# ORing_block.net
KiCad netlist of a schematic drawn in EAGLE
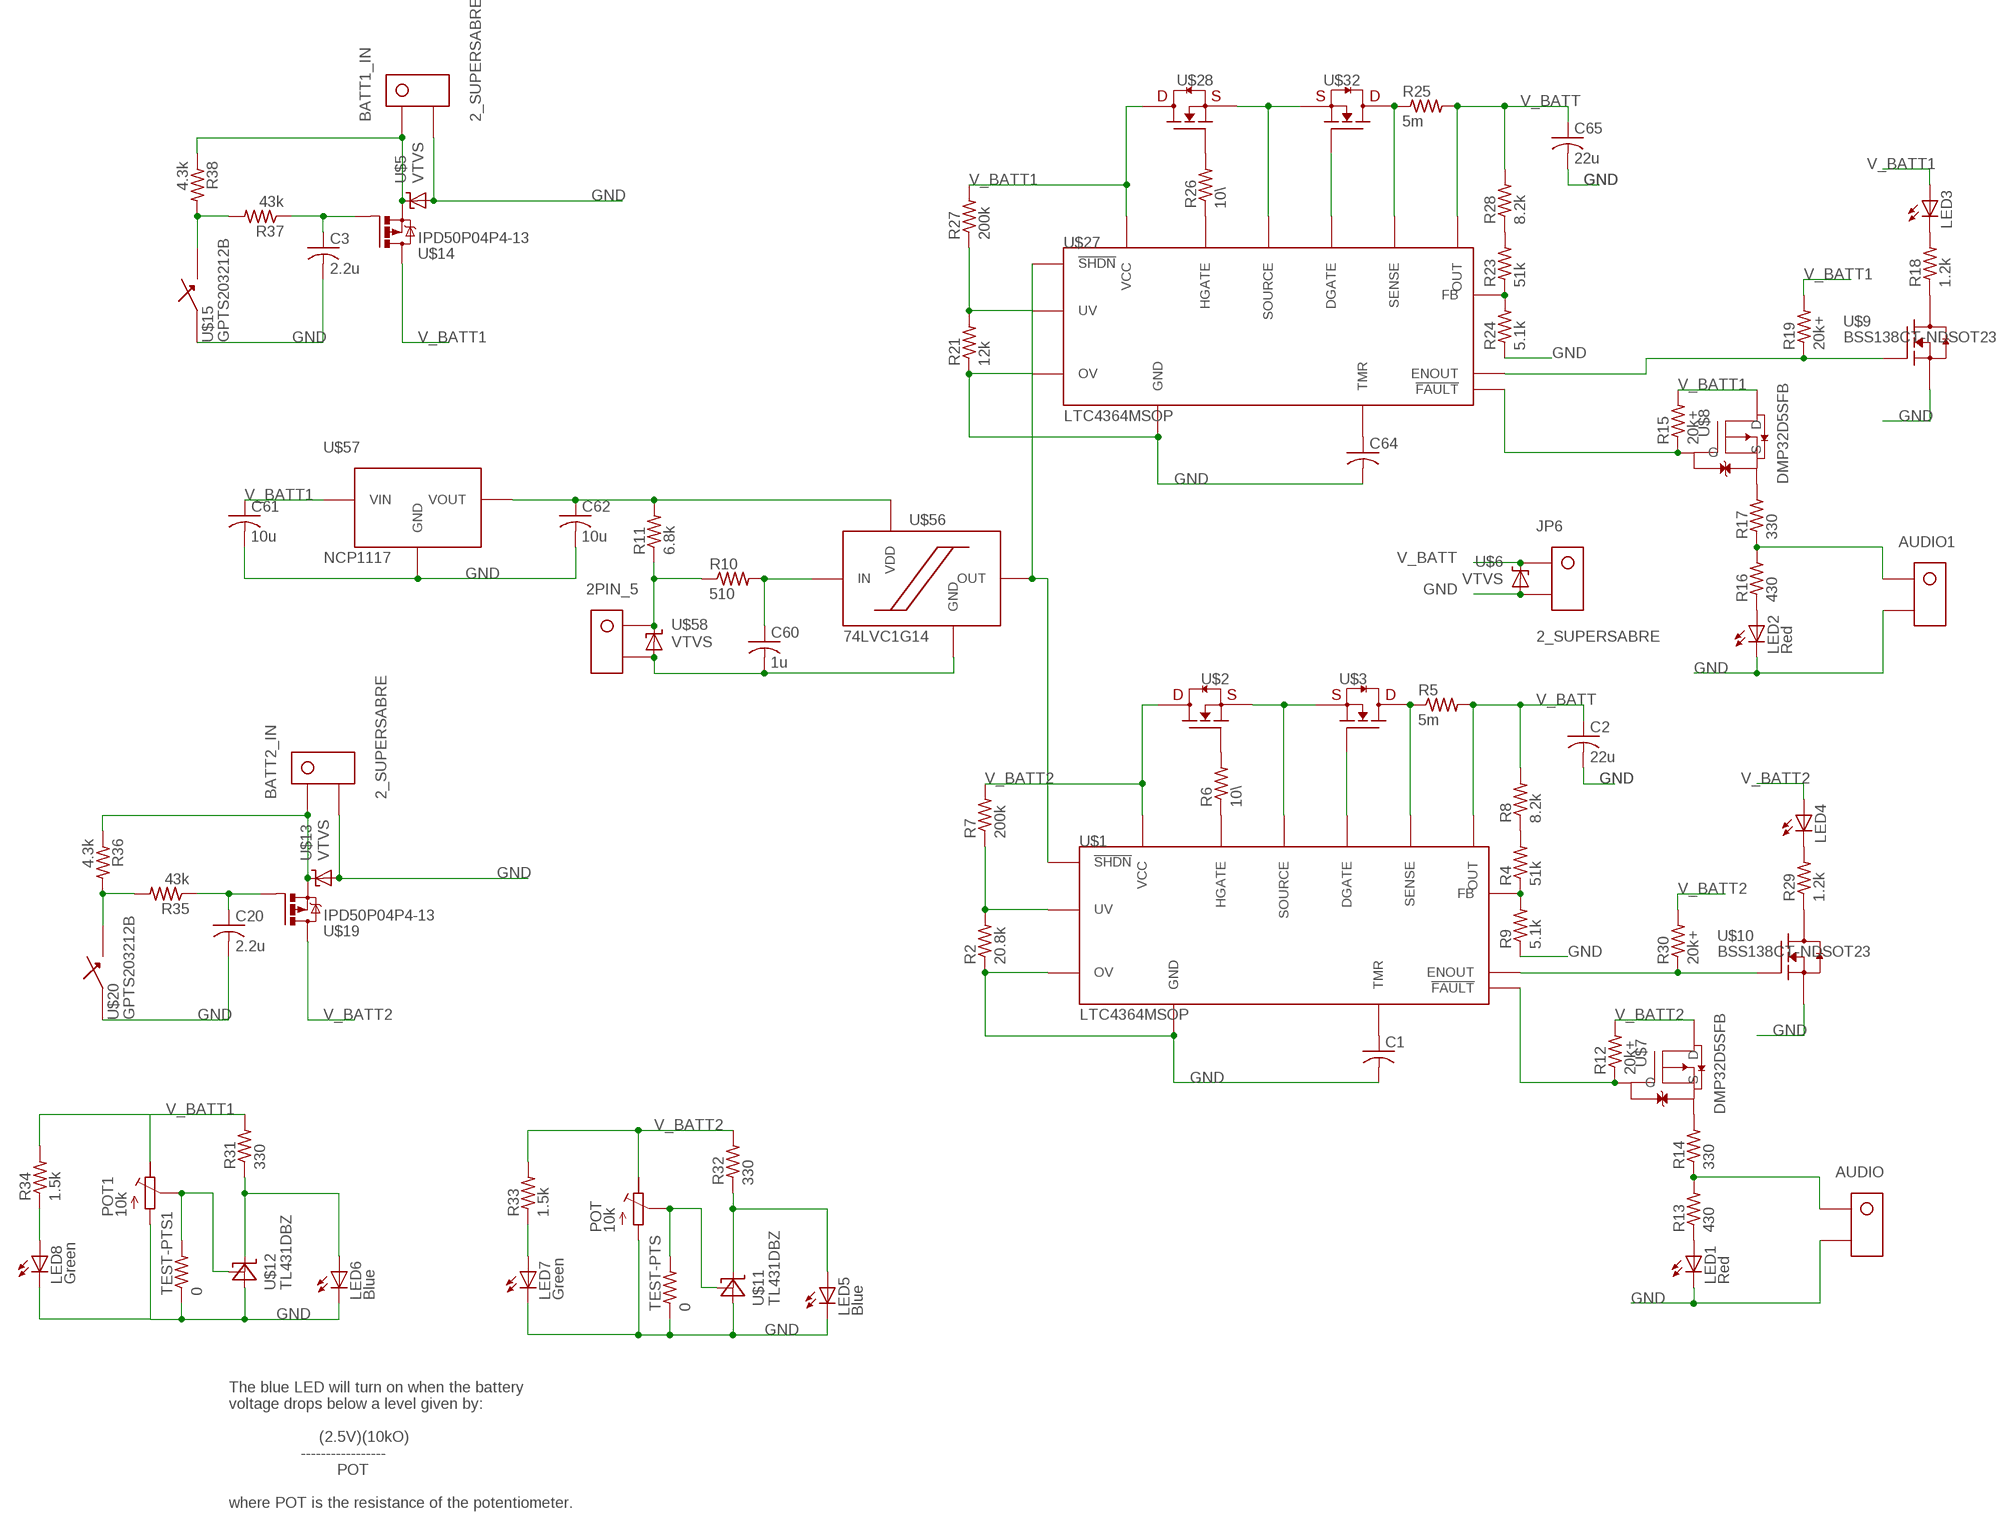
[diagram p0: schematic, sheet 1]

(export (version "E")
  (design (tool "Eeschema 10.0.6"))
  (components
    (comp (ref "2PIN_5")
      (value "KK254_VERT_2PIN22-29-2021")
      (footprint "eagle-import:KK254_VERT_2PIN")
      (libsource (lib "eagle-import") (part "KK254_VERT_2PIN22-29-2021"))
    )
    (comp (ref "AUDIO")
      (value "KK254_VERT_2PIN22-29-2021")
      (footprint "eagle-import:KK254_VERT_2PIN")
      (libsource (lib "eagle-import") (part "KK254_VERT_2PIN22-29-2021"))
    )
    (comp (ref "AUDIO1")
      (value "KK254_VERT_2PIN22-29-2021")
      (footprint "eagle-import:KK254_VERT_2PIN")
      (libsource (lib "eagle-import") (part "KK254_VERT_2PIN22-29-2021"))
    )
    (comp (ref "BATT1_IN")
      (value "2_SUPERSABRE")
      (footprint "eagle-import:SUPERSABRE_2CIRCUIT")
      (libsource (lib "eagle-import") (part "2_SUPERSABRE"))
    )
    (comp (ref "BATT2_IN")
      (value "2_SUPERSABRE")
      (footprint "eagle-import:SUPERSABRE_2CIRCUIT")
      (libsource (lib "eagle-import") (part "2_SUPERSABRE"))
    )
    (comp (ref "C1")
      (value "C-USC0805")
      (footprint "eagle-import:C0805")
      (libsource (lib "eagle-import") (part "C-USC0805"))
    )
    (comp (ref "C2")
      (value "22u")
      (footprint "eagle-import:C0805")
      (libsource (lib "eagle-import") (part "C-USC0805"))
    )
    (comp (ref "C3")
      (value "2.2u")
      (footprint "eagle-import:C0805")
      (libsource (lib "eagle-import") (part "C-USC0805"))
    )
    (comp (ref "C20")
      (value "2.2u")
      (footprint "eagle-import:C0805")
      (libsource (lib "eagle-import") (part "C-USC0805"))
    )
    (comp (ref "C60")
      (value "1u")
      (footprint "eagle-import:C0805")
      (libsource (lib "eagle-import") (part "C-USC0805"))
    )
    (comp (ref "C61")
      (value "10u")
      (footprint "eagle-import:C0805")
      (libsource (lib "eagle-import") (part "C-USC0805"))
    )
    (comp (ref "C62")
      (value "10u")
      (footprint "eagle-import:C0805")
      (libsource (lib "eagle-import") (part "C-USC0805"))
    )
    (comp (ref "C64")
      (value "C-USC0805")
      (footprint "eagle-import:C0805")
      (libsource (lib "eagle-import") (part "C-USC0805"))
    )
    (comp (ref "C65")
      (value "22u")
      (footprint "eagle-import:C0805")
      (libsource (lib "eagle-import") (part "C-USC0805"))
    )
    (comp (ref "JP6")
      (value "2_SUPERSABRE")
      (footprint "eagle-import:SUPERSABRE_2CIRCUIT")
      (libsource (lib "eagle-import") (part "2_SUPERSABRE"))
    )
    (comp (ref "LED1")
      (value "Red")
      (footprint "eagle-import:CHIPLED_0805")
      (libsource (lib "eagle-import") (part "LEDCHIPLED_0805"))
    )
    (comp (ref "LED2")
      (value "Red")
      (footprint "eagle-import:CHIPLED_0805")
      (libsource (lib "eagle-import") (part "LEDCHIPLED_0805"))
    )
    (comp (ref "LED3")
      (value "LEDCHIPLED_0805")
      (footprint "eagle-import:CHIPLED_0805")
      (libsource (lib "eagle-import") (part "LEDCHIPLED_0805"))
    )
    (comp (ref "LED4")
      (value "LEDCHIPLED_0805")
      (footprint "eagle-import:CHIPLED_0805")
      (libsource (lib "eagle-import") (part "LEDCHIPLED_0805"))
    )
    (comp (ref "LED5")
      (value "Blue")
      (footprint "eagle-import:0805")
      (libsource (lib "eagle-import") (part "0805_LED"))
    )
    (comp (ref "LED6")
      (value "Blue")
      (footprint "eagle-import:0805")
      (libsource (lib "eagle-import") (part "0805_LED"))
    )
    (comp (ref "LED7")
      (value "Green")
      (footprint "eagle-import:0805")
      (libsource (lib "eagle-import") (part "0805_LED"))
    )
    (comp (ref "LED8")
      (value "Green")
      (footprint "eagle-import:0805")
      (libsource (lib "eagle-import") (part "0805_LED"))
    )
    (comp (ref "POT")
      (value "10k")
      (footprint "eagle-import:PTV09A-4")
      (libsource (lib "eagle-import") (part "R-TRIMMPTV09A-4"))
    )
    (comp (ref "POT1")
      (value "10k")
      (footprint "eagle-import:PTV09A-4")
      (libsource (lib "eagle-import") (part "R-TRIMMPTV09A-4"))
    )
    (comp (ref "R2")
      (value "20.8k")
      (footprint "eagle-import:R0805")
      (libsource (lib "eagle-import") (part "R-US_R0805"))
    )
    (comp (ref "R4")
      (value "51k")
      (footprint "eagle-import:R0805")
      (libsource (lib "eagle-import") (part "R-US_R0805"))
    )
    (comp (ref "R5")
      (value "5m")
      (footprint "eagle-import:R0805")
      (libsource (lib "eagle-import") (part "R-US_R0805"))
    )
    (comp (ref "R6")
      (value "10\\")
      (footprint "eagle-import:R0805")
      (libsource (lib "eagle-import") (part "R-US_R0805"))
    )
    (comp (ref "R7")
      (value "200k")
      (footprint "eagle-import:R0805")
      (libsource (lib "eagle-import") (part "R-US_R0805"))
    )
    (comp (ref "R8")
      (value "8.2k")
      (footprint "eagle-import:R0805")
      (libsource (lib "eagle-import") (part "R-US_R0805"))
    )
    (comp (ref "R9")
      (value "5.1k")
      (footprint "eagle-import:R0805")
      (libsource (lib "eagle-import") (part "R-US_R0805"))
    )
    (comp (ref "R10")
      (value "510")
      (footprint "eagle-import:R0805")
      (libsource (lib "eagle-import") (part "R-US_R0805"))
    )
    (comp (ref "R11")
      (value "6.8k")
      (footprint "eagle-import:R0805")
      (libsource (lib "eagle-import") (part "R-US_R0805"))
    )
    (comp (ref "R12")
      (value "20k+")
      (footprint "eagle-import:R0805")
      (libsource (lib "eagle-import") (part "R-US_R0805"))
    )
    (comp (ref "R13")
      (value "430")
      (footprint "eagle-import:R0805")
      (libsource (lib "eagle-import") (part "R-US_R0805"))
    )
    (comp (ref "R14")
      (value "330")
      (footprint "eagle-import:R0805")
      (libsource (lib "eagle-import") (part "R-US_R0805"))
    )
    (comp (ref "R15")
      (value "20k+")
      (footprint "eagle-import:R0805")
      (libsource (lib "eagle-import") (part "R-US_R0805"))
    )
    (comp (ref "R16")
      (value "430")
      (footprint "eagle-import:R0805")
      (libsource (lib "eagle-import") (part "R-US_R0805"))
    )
    (comp (ref "R17")
      (value "330")
      (footprint "eagle-import:R0805")
      (libsource (lib "eagle-import") (part "R-US_R0805"))
    )
    (comp (ref "R18")
      (value "1.2k")
      (footprint "eagle-import:R0805")
      (libsource (lib "eagle-import") (part "R-US_R0805"))
    )
    (comp (ref "R19")
      (value "20k+")
      (footprint "eagle-import:R0805")
      (libsource (lib "eagle-import") (part "R-US_R0805"))
    )
    (comp (ref "R21")
      (value "12k")
      (footprint "eagle-import:R0805")
      (libsource (lib "eagle-import") (part "R-US_R0805"))
    )
    (comp (ref "R23")
      (value "51k")
      (footprint "eagle-import:R0805")
      (libsource (lib "eagle-import") (part "R-US_R0805"))
    )
    (comp (ref "R24")
      (value "5.1k")
      (footprint "eagle-import:R0805")
      (libsource (lib "eagle-import") (part "R-US_R0805"))
    )
    (comp (ref "R25")
      (value "5m")
      (footprint "eagle-import:R0805")
      (libsource (lib "eagle-import") (part "R-US_R0805"))
    )
    (comp (ref "R26")
      (value "10\\")
      (footprint "eagle-import:R0805")
      (libsource (lib "eagle-import") (part "R-US_R0805"))
    )
    (comp (ref "R27")
      (value "200k")
      (footprint "eagle-import:R0805")
      (libsource (lib "eagle-import") (part "R-US_R0805"))
    )
    (comp (ref "R28")
      (value "8.2k")
      (footprint "eagle-import:R0805")
      (libsource (lib "eagle-import") (part "R-US_R0805"))
    )
    (comp (ref "R29")
      (value "1.2k")
      (footprint "eagle-import:R0805")
      (libsource (lib "eagle-import") (part "R-US_R0805"))
    )
    (comp (ref "R30")
      (value "20k+")
      (footprint "eagle-import:R0805")
      (libsource (lib "eagle-import") (part "R-US_R0805"))
    )
    (comp (ref "R31")
      (value "330")
      (footprint "eagle-import:R0805")
      (libsource (lib "eagle-import") (part "R-US_R0805"))
    )
    (comp (ref "R32")
      (value "330")
      (footprint "eagle-import:R0805")
      (libsource (lib "eagle-import") (part "R-US_R0805"))
    )
    (comp (ref "R33")
      (value "1.5k")
      (footprint "eagle-import:R0805")
      (libsource (lib "eagle-import") (part "R-US_R0805"))
    )
    (comp (ref "R34")
      (value "1.5k")
      (footprint "eagle-import:R0805")
      (libsource (lib "eagle-import") (part "R-US_R0805"))
    )
    (comp (ref "R35")
      (value "43k")
      (footprint "eagle-import:R0805")
      (libsource (lib "eagle-import") (part "R-US_R0805"))
    )
    (comp (ref "R36")
      (value "4.3k")
      (footprint "eagle-import:R0805")
      (libsource (lib "eagle-import") (part "R-US_R0805"))
    )
    (comp (ref "R37")
      (value "43k")
      (footprint "eagle-import:R0805")
      (libsource (lib "eagle-import") (part "R-US_R0805"))
    )
    (comp (ref "R38")
      (value "4.3k")
      (footprint "eagle-import:R0805")
      (libsource (lib "eagle-import") (part "R-US_R0805"))
    )
    (comp (ref "TEST-PTS")
      (value "0")
      (footprint "eagle-import:V526-0")
      (libsource (lib "eagle-import") (part "R-US_V526-0"))
    )
    (comp (ref "TEST-PTS1")
      (value "0")
      (footprint "eagle-import:V526-0")
      (libsource (lib "eagle-import") (part "R-US_V526-0"))
    )
    (comp (ref "U$1")
      (value "LTC4364MSOP")
      (footprint "eagle-import:MSOP16")
      (libsource (lib "eagle-import") (part "LTC4364MSOP"))
    )
    (comp (ref "U$2")
      (value "FDMC8360LET40PWR33")
      (footprint "eagle-import:POWER33")
      (libsource (lib "eagle-import") (part "FDMC8360LET40PWR33"))
    )
    (comp (ref "U$3")
      (value "FDMC8360LET40PWR33")
      (footprint "eagle-import:POWER33")
      (libsource (lib "eagle-import") (part "FDMC8360LET40PWR33"))
    )
    (comp (ref "U$5")
      (value "VTVS")
      (footprint "eagle-import:DO-219AB")
      (libsource (lib "eagle-import") (part "VTVS"))
    )
    (comp (ref "U$6")
      (value "VTVS")
      (footprint "eagle-import:DO-219AB")
      (libsource (lib "eagle-import") (part "VTVS"))
    )
    (comp (ref "U$7")
      (value "DMP32D5SFB")
      (footprint "eagle-import:AP02002")
      (libsource (lib "eagle-import") (part "DMP32D5SFB"))
    )
    (comp (ref "U$8")
      (value "DMP32D5SFB")
      (footprint "eagle-import:AP02002")
      (libsource (lib "eagle-import") (part "DMP32D5SFB"))
    )
    (comp (ref "U$9")
      (value "BSS138CT-NDSOT23")
      (footprint "eagle-import:SOT23")
      (libsource (lib "eagle-import") (part "BSS138CT-NDSOT23"))
    )
    (comp (ref "U$10")
      (value "BSS138CT-NDSOT23")
      (footprint "eagle-import:SOT23")
      (libsource (lib "eagle-import") (part "BSS138CT-NDSOT23"))
    )
    (comp (ref "U$11")
      (value "TL431DBZ")
      (footprint "eagle-import:SOT-23-3")
      (libsource (lib "eagle-import") (part "TL431DBZ"))
    )
    (comp (ref "U$12")
      (value "TL431DBZ")
      (footprint "eagle-import:SOT-23-3")
      (libsource (lib "eagle-import") (part "TL431DBZ"))
    )
    (comp (ref "U$13")
      (value "VTVS")
      (footprint "eagle-import:DO-219AB")
      (libsource (lib "eagle-import") (part "VTVS"))
    )
    (comp (ref "U$14")
      (value "IPD50P04P4-13")
      (footprint "eagle-import:TO252-3")
      (libsource (lib "eagle-import") (part "IPD50P04P4-13"))
    )
    (comp (ref "U$15")
      (value "GPTS203212B")
      (footprint "eagle-import:GPTS203211B")
      (libsource (lib "eagle-import") (part "GPTS203212B"))
    )
    (comp (ref "U$19")
      (value "IPD50P04P4-13")
      (footprint "eagle-import:TO252-3")
      (libsource (lib "eagle-import") (part "IPD50P04P4-13"))
    )
    (comp (ref "U$20")
      (value "GPTS203212B")
      (footprint "eagle-import:GPTS203211B")
      (libsource (lib "eagle-import") (part "GPTS203212B"))
    )
    (comp (ref "U$27")
      (value "LTC4364MSOP")
      (footprint "eagle-import:MSOP16")
      (libsource (lib "eagle-import") (part "LTC4364MSOP"))
    )
    (comp (ref "U$28")
      (value "FDMC8360LET40PWR33")
      (footprint "eagle-import:POWER33")
      (libsource (lib "eagle-import") (part "FDMC8360LET40PWR33"))
    )
    (comp (ref "U$32")
      (value "FDMC8360LET40PWR33")
      (footprint "eagle-import:POWER33")
      (libsource (lib "eagle-import") (part "FDMC8360LET40PWR33"))
    )
    (comp (ref "U$56")
      (value "74LVC1G14")
      (footprint "eagle-import:TSSOP5")
      (libsource (lib "eagle-import") (part "74LVC1G14"))
    )
    (comp (ref "U$57")
      (value "NCP1117")
      (footprint "eagle-import:SOT-223")
      (libsource (lib "eagle-import") (part "NCP1117"))
    )
    (comp (ref "U$58")
      (value "VTVS")
      (footprint "eagle-import:DO-219AB")
      (libsource (lib "eagle-import") (part "VTVS"))
    )
  )
  (nets
    (net (code "1") (name "/GND") (class "Default")
      (node (ref "AUDIO") (pin "P$2") (pinfunction "P$2_P$2") (pintype "bidirectional"))
      (node (ref "AUDIO1") (pin "P$2") (pinfunction "P$2_P$2") (pintype "bidirectional"))
      (node (ref "BATT1_IN") (pin "P$2") (pinfunction "P$2_P$2") (pintype "bidirectional"))
      (node (ref "BATT2_IN") (pin "P$2") (pinfunction "P$2_P$2") (pintype "bidirectional"))
      (node (ref "C1") (pin "2") (pinfunction "2_2") (pintype "passive"))
      (node (ref "C2") (pin "2") (pinfunction "2_2") (pintype "passive"))
      (node (ref "C20") (pin "2") (pinfunction "2_2") (pintype "passive"))
      (node (ref "C3") (pin "2") (pinfunction "2_2") (pintype "passive"))
      (node (ref "C61") (pin "2") (pinfunction "2_2") (pintype "passive"))
      (node (ref "C62") (pin "2") (pinfunction "2_2") (pintype "passive"))
      (node (ref "C64") (pin "2") (pinfunction "2_2") (pintype "passive"))
      (node (ref "C65") (pin "2") (pinfunction "2_2") (pintype "passive"))
      (node (ref "JP6") (pin "P$2") (pinfunction "P$2_P$2") (pintype "bidirectional"))
      (node (ref "LED1") (pin "C") (pinfunction "C_C") (pintype "passive"))
      (node (ref "LED2") (pin "C") (pinfunction "C_C") (pintype "passive"))
      (node (ref "LED5") (pin "P$2") (pinfunction "C_P$2") (pintype "passive"))
      (node (ref "LED6") (pin "P$2") (pinfunction "C_P$2") (pintype "passive"))
      (node (ref "LED7") (pin "P$2") (pinfunction "C_P$2") (pintype "passive"))
      (node (ref "LED8") (pin "P$2") (pinfunction "C_P$2") (pintype "passive"))
      (node (ref "POT") (pin "P$3") (pinfunction "E_P$3") (pintype "passive"))
      (node (ref "POT1") (pin "P$3") (pinfunction "E_P$3") (pintype "passive"))
      (node (ref "R2") (pin "1") (pinfunction "1_1") (pintype "passive"))
      (node (ref "R21") (pin "1") (pinfunction "1_1") (pintype "passive"))
      (node (ref "R24") (pin "1") (pinfunction "1_1") (pintype "passive"))
      (node (ref "R9") (pin "1") (pinfunction "1_1") (pintype "passive"))
      (node (ref "TEST-PTS") (pin "1") (pinfunction "1_1") (pintype "passive"))
      (node (ref "TEST-PTS1") (pin "1") (pinfunction "1_1") (pintype "passive"))
      (node (ref "U$1") (pin "GND") (pinfunction "GND_GND") (pintype "bidirectional"))
      (node (ref "U$1") (pin "OV") (pinfunction "OV_OV") (pintype "bidirectional"))
      (node (ref "U$10") (pin "2") (pinfunction "S_2") (pintype "passive"))
      (node (ref "U$11") (pin "P$3") (pinfunction "A_P$3") (pintype "passive"))
      (node (ref "U$12") (pin "P$3") (pinfunction "A_P$3") (pintype "passive"))
      (node (ref "U$13") (pin "P$1") (pinfunction "A_P$1") (pintype "passive"))
      (node (ref "U$15") (pin "P$1") (pinfunction "P$1_P$1") (pintype "bidirectional"))
      (node (ref "U$20") (pin "P$1") (pinfunction "P$1_P$1") (pintype "bidirectional"))
      (node (ref "U$27") (pin "GND") (pinfunction "GND_GND") (pintype "bidirectional"))
      (node (ref "U$27") (pin "OV") (pinfunction "OV_OV") (pintype "bidirectional"))
      (node (ref "U$5") (pin "P$1") (pinfunction "A_P$1") (pintype "passive"))
      (node (ref "U$57") (pin "P$1") (pinfunction "GND_P$1") (pintype "bidirectional"))
      (node (ref "U$6") (pin "P$1") (pinfunction "A_P$1") (pintype "passive"))
      (node (ref "U$9") (pin "2") (pinfunction "S_2") (pintype "passive"))
    )
    (net (code "2") (name "/V_BATT") (class "Default")
      (node (ref "C2") (pin "1") (pinfunction "1_1") (pintype "passive"))
      (node (ref "C65") (pin "1") (pinfunction "1_1") (pintype "passive"))
      (node (ref "JP6") (pin "P$1") (pinfunction "P$1_P$1") (pintype "bidirectional"))
      (node (ref "R25") (pin "2") (pinfunction "2_2") (pintype "passive"))
      (node (ref "R28") (pin "2") (pinfunction "2_2") (pintype "passive"))
      (node (ref "R5") (pin "2") (pinfunction "2_2") (pintype "passive"))
      (node (ref "R8") (pin "2") (pinfunction "2_2") (pintype "passive"))
      (node (ref "U$1") (pin "OUT") (pinfunction "OUT_OUT") (pintype "bidirectional"))
      (node (ref "U$27") (pin "OUT") (pinfunction "OUT_OUT") (pintype "bidirectional"))
      (node (ref "U$6") (pin "P$2") (pinfunction "C_P$2") (pintype "passive"))
    )
    (net (code "3") (name "/V_BATT1") (class "Default")
      (node (ref "C61") (pin "1") (pinfunction "1_1") (pintype "passive"))
      (node (ref "LED3") (pin "A") (pinfunction "A_A") (pintype "passive"))
      (node (ref "POT1") (pin "P$1") (pinfunction "A_P$1") (pintype "passive"))
      (node (ref "R15") (pin "2") (pinfunction "2_2") (pintype "passive"))
      (node (ref "R19") (pin "2") (pinfunction "2_2") (pintype "passive"))
      (node (ref "R27") (pin "2") (pinfunction "2_2") (pintype "passive"))
      (node (ref "R31") (pin "2") (pinfunction "2_2") (pintype "passive"))
      (node (ref "R34") (pin "2") (pinfunction "2_2") (pintype "passive"))
      (node (ref "U$14") (pin "3") (pinfunction "S_3") (pintype "passive"))
      (node (ref "U$27") (pin "VCC") (pinfunction "VCC_VCC") (pintype "bidirectional"))
      (node (ref "U$28") (pin "DRAIN") (pinfunction "DRAIN_DRAIN") (pintype "bidirectional"))
      (node (ref "U$57") (pin "P$3") (pinfunction "VIN_P$3") (pintype "bidirectional"))
      (node (ref "U$8") (pin "P$3") (pinfunction "D_P$3") (pintype "bidirectional"))
    )
    (net (code "4") (name "/V_BATT2") (class "Default")
      (node (ref "LED4") (pin "A") (pinfunction "A_A") (pintype "passive"))
      (node (ref "POT") (pin "P$1") (pinfunction "A_P$1") (pintype "passive"))
      (node (ref "R12") (pin "2") (pinfunction "2_2") (pintype "passive"))
      (node (ref "R30") (pin "2") (pinfunction "2_2") (pintype "passive"))
      (node (ref "R32") (pin "2") (pinfunction "2_2") (pintype "passive"))
      (node (ref "R33") (pin "2") (pinfunction "2_2") (pintype "passive"))
      (node (ref "R7") (pin "2") (pinfunction "2_2") (pintype "passive"))
      (node (ref "U$1") (pin "VCC") (pinfunction "VCC_VCC") (pintype "bidirectional"))
      (node (ref "U$19") (pin "3") (pinfunction "S_3") (pintype "passive"))
      (node (ref "U$2") (pin "DRAIN") (pinfunction "DRAIN_DRAIN") (pintype "bidirectional"))
      (node (ref "U$7") (pin "P$3") (pinfunction "D_P$3") (pintype "bidirectional"))
    )
    (net (code "5") (name "Net-(AUDIO-PadP$1)") (class "Default")
      (node (ref "AUDIO") (pin "P$1") (pinfunction "P$1_P$1") (pintype "bidirectional"))
      (node (ref "R13") (pin "2") (pinfunction "2_2") (pintype "passive"))
      (node (ref "R14") (pin "1") (pinfunction "1_1") (pintype "passive"))
    )
    (net (code "6") (name "Net-(AUDIO1-PadP$1)") (class "Default")
      (node (ref "AUDIO1") (pin "P$1") (pinfunction "P$1_P$1") (pintype "bidirectional"))
      (node (ref "R16") (pin "2") (pinfunction "2_2") (pintype "passive"))
      (node (ref "R17") (pin "1") (pinfunction "1_1") (pintype "passive"))
    )
    (net (code "7") (name "Net-(C1-Pad1)") (class "Default")
      (node (ref "C1") (pin "1") (pinfunction "1_1") (pintype "passive"))
      (node (ref "U$1") (pin "TMR") (pinfunction "TMR_TMR") (pintype "bidirectional"))
    )
    (net (code "8") (name "Net-(C64-Pad1)") (class "Default")
      (node (ref "C64") (pin "1") (pinfunction "1_1") (pintype "passive"))
      (node (ref "U$27") (pin "TMR") (pinfunction "TMR_TMR") (pintype "bidirectional"))
    )
    (net (code "9") (name "Net-(LED1-PadA)") (class "Default")
      (node (ref "LED1") (pin "A") (pinfunction "A_A") (pintype "passive"))
      (node (ref "R13") (pin "1") (pinfunction "1_1") (pintype "passive"))
    )
    (net (code "10") (name "Net-(LED2-PadA)") (class "Default")
      (node (ref "LED2") (pin "A") (pinfunction "A_A") (pintype "passive"))
      (node (ref "R16") (pin "1") (pinfunction "1_1") (pintype "passive"))
    )
    (net (code "11") (name "Net-(LED3-PadC)") (class "Default")
      (node (ref "LED3") (pin "C") (pinfunction "C_C") (pintype "passive"))
      (node (ref "R18") (pin "2") (pinfunction "2_2") (pintype "passive"))
    )
    (net (code "12") (name "Net-(LED4-PadC)") (class "Default")
      (node (ref "LED4") (pin "C") (pinfunction "C_C") (pintype "passive"))
      (node (ref "R29") (pin "2") (pinfunction "2_2") (pintype "passive"))
    )
    (net (code "13") (name "Net-(LED5-A)") (class "Default")
      (node (ref "LED5") (pin "P$1") (pinfunction "A_P$1") (pintype "passive"))
      (node (ref "R32") (pin "1") (pinfunction "1_1") (pintype "passive"))
      (node (ref "U$11") (pin "P$1") (pinfunction "C_P$1") (pintype "passive"))
    )
    (net (code "14") (name "Net-(LED6-A)") (class "Default")
      (node (ref "LED6") (pin "P$1") (pinfunction "A_P$1") (pintype "passive"))
      (node (ref "R31") (pin "1") (pinfunction "1_1") (pintype "passive"))
      (node (ref "U$12") (pin "P$1") (pinfunction "C_P$1") (pintype "passive"))
    )
    (net (code "15") (name "Net-(LED7-A)") (class "Default")
      (node (ref "LED7") (pin "P$1") (pinfunction "A_P$1") (pintype "passive"))
      (node (ref "R33") (pin "1") (pinfunction "1_1") (pintype "passive"))
    )
    (net (code "16") (name "Net-(LED8-A)") (class "Default")
      (node (ref "LED8") (pin "P$1") (pinfunction "A_P$1") (pintype "passive"))
      (node (ref "R34") (pin "1") (pinfunction "1_1") (pintype "passive"))
    )
    (net (code "17") (name "Net-(POT-S)") (class "Default")
      (node (ref "POT") (pin "P$2") (pinfunction "S_P$2") (pintype "passive"))
      (node (ref "TEST-PTS") (pin "2") (pinfunction "2_2") (pintype "passive"))
      (node (ref "U$11") (pin "P$2") (pinfunction "REF_P$2") (pintype "bidirectional"))
    )
    (net (code "18") (name "Net-(POT1-S)") (class "Default")
      (node (ref "POT1") (pin "P$2") (pinfunction "S_P$2") (pintype "passive"))
      (node (ref "TEST-PTS1") (pin "2") (pinfunction "2_2") (pintype "passive"))
      (node (ref "U$12") (pin "P$2") (pinfunction "REF_P$2") (pintype "bidirectional"))
    )
    (net (code "19") (name "Net-(R2-Pad2)") (class "Default")
      (node (ref "R2") (pin "2") (pinfunction "2_2") (pintype "passive"))
      (node (ref "R7") (pin "1") (pinfunction "1_1") (pintype "passive"))
      (node (ref "U$1") (pin "UV") (pinfunction "UV_UV") (pintype "bidirectional"))
    )
    (net (code "20") (name "Net-(R4-Pad1)") (class "Default")
      (node (ref "R4") (pin "1") (pinfunction "1_1") (pintype "passive"))
      (node (ref "R9") (pin "2") (pinfunction "2_2") (pintype "passive"))
      (node (ref "U$1") (pin "FB") (pinfunction "FB_FB") (pintype "bidirectional"))
    )
    (net (code "21") (name "Net-(R4-Pad2)") (class "Default")
      (node (ref "R4") (pin "2") (pinfunction "2_2") (pintype "passive"))
      (node (ref "R8") (pin "1") (pinfunction "1_1") (pintype "passive"))
    )
    (net (code "22") (name "Net-(R5-Pad1)") (class "Default")
      (node (ref "R5") (pin "1") (pinfunction "1_1") (pintype "passive"))
      (node (ref "U$1") (pin "SENSE") (pinfunction "SENSE_SENSE") (pintype "bidirectional"))
      (node (ref "U$3") (pin "DRAIN") (pinfunction "DRAIN_DRAIN") (pintype "bidirectional"))
    )
    (net (code "23") (name "Net-(R6-Pad1)") (class "Default")
      (node (ref "R6") (pin "1") (pinfunction "1_1") (pintype "passive"))
      (node (ref "U$1") (pin "HGATE") (pinfunction "HGATE_HGATE") (pintype "bidirectional"))
    )
    (net (code "24") (name "Net-(R6-Pad2)") (class "Default")
      (node (ref "R6") (pin "2") (pinfunction "2_2") (pintype "passive"))
      (node (ref "U$2") (pin "GATE") (pinfunction "GATE_GATE") (pintype "passive"))
    )
    (net (code "25") (name "Net-(R21-Pad2)") (class "Default")
      (node (ref "R21") (pin "2") (pinfunction "2_2") (pintype "passive"))
      (node (ref "R27") (pin "1") (pinfunction "1_1") (pintype "passive"))
      (node (ref "U$27") (pin "UV") (pinfunction "UV_UV") (pintype "bidirectional"))
    )
    (net (code "26") (name "Net-(R23-Pad1)") (class "Default")
      (node (ref "R23") (pin "1") (pinfunction "1_1") (pintype "passive"))
      (node (ref "R24") (pin "2") (pinfunction "2_2") (pintype "passive"))
      (node (ref "U$27") (pin "FB") (pinfunction "FB_FB") (pintype "bidirectional"))
    )
    (net (code "27") (name "Net-(R23-Pad2)") (class "Default")
      (node (ref "R23") (pin "2") (pinfunction "2_2") (pintype "passive"))
      (node (ref "R28") (pin "1") (pinfunction "1_1") (pintype "passive"))
    )
    (net (code "28") (name "Net-(R25-Pad1)") (class "Default")
      (node (ref "R25") (pin "1") (pinfunction "1_1") (pintype "passive"))
      (node (ref "U$27") (pin "SENSE") (pinfunction "SENSE_SENSE") (pintype "bidirectional"))
      (node (ref "U$32") (pin "DRAIN") (pinfunction "DRAIN_DRAIN") (pintype "bidirectional"))
    )
    (net (code "29") (name "Net-(R26-Pad1)") (class "Default")
      (node (ref "R26") (pin "1") (pinfunction "1_1") (pintype "passive"))
      (node (ref "U$27") (pin "HGATE") (pinfunction "HGATE_HGATE") (pintype "bidirectional"))
    )
    (net (code "30") (name "Net-(R26-Pad2)") (class "Default")
      (node (ref "R26") (pin "2") (pinfunction "2_2") (pintype "passive"))
      (node (ref "U$28") (pin "GATE") (pinfunction "GATE_GATE") (pintype "passive"))
    )
    (net (code "31") (name "Net-(R35-Pad2)") (class "Default")
      (node (ref "R35") (pin "2") (pinfunction "2_2") (pintype "passive"))
      (node (ref "R36") (pin "2") (pinfunction "2_2") (pintype "passive"))
      (node (ref "U$20") (pin "P$2") (pinfunction "P$2_P$2") (pintype "bidirectional"))
    )
    (net (code "32") (name "Net-(R37-Pad2)") (class "Default")
      (node (ref "R37") (pin "2") (pinfunction "2_2") (pintype "passive"))
      (node (ref "R38") (pin "2") (pinfunction "2_2") (pintype "passive"))
      (node (ref "U$15") (pin "P$2") (pinfunction "P$2_P$2") (pintype "bidirectional"))
    )
    (net (code "33") (name "Net-(U$1-PadDGATE)") (class "Default")
      (node (ref "U$1") (pin "DGATE") (pinfunction "DGATE_DGATE") (pintype "bidirectional"))
      (node (ref "U$3") (pin "GATE") (pinfunction "GATE_GATE") (pintype "passive"))
    )
    (net (code "34") (name "Net-(U$1-PadSOURCE)") (class "Default")
      (node (ref "U$1") (pin "SOURCE") (pinfunction "SOURCE_SOURCE") (pintype "bidirectional"))
      (node (ref "U$2") (pin "SOURCE1") (pinfunction "SOURCE_SOURCE1") (pintype "passive"))
      (node (ref "U$2") (pin "SOURCE2") (pinfunction "SOURCE_SOURCE2") (pintype "passive"))
      (node (ref "U$2") (pin "SOURCE3") (pinfunction "SOURCE_SOURCE3") (pintype "passive"))
      (node (ref "U$3") (pin "SOURCE1") (pinfunction "SOURCE_SOURCE1") (pintype "passive"))
      (node (ref "U$3") (pin "SOURCE2") (pinfunction "SOURCE_SOURCE2") (pintype "passive"))
      (node (ref "U$3") (pin "SOURCE3") (pinfunction "SOURCE_SOURCE3") (pintype "passive"))
    )
    (net (code "35") (name "Net-(U$1-~{FAULT})") (class "Default")
      (node (ref "R12") (pin "1") (pinfunction "1_1") (pintype "passive"))
      (node (ref "U$1") (pin "FLT") (pinfunction "~{FAULT}_FLT") (pintype "bidirectional"))
      (node (ref "U$7") (pin "P$2") (pinfunction "G_P$2") (pintype "bidirectional"))
    )
    (net (code "36") (name "Net-(U$1-~{SHDN})") (class "Default")
      (node (ref "U$1") (pin "SHDN") (pinfunction "~{SHDN}_SHDN") (pintype "bidirectional"))
      (node (ref "U$27") (pin "SHDN") (pinfunction "~{SHDN}_SHDN") (pintype "bidirectional"))
      (node (ref "U$56") (pin "P$4") (pinfunction "OUT_P$4") (pintype "bidirectional"))
    )
    (net (code "37") (name "Net-(U$7-S)") (class "Default")
      (node (ref "R14") (pin "2") (pinfunction "2_2") (pintype "passive"))
      (node (ref "U$7") (pin "P$1") (pinfunction "S_P$1") (pintype "bidirectional"))
    )
    (net (code "38") (name "Net-(U$8-S)") (class "Default")
      (node (ref "R17") (pin "2") (pinfunction "2_2") (pintype "passive"))
      (node (ref "U$8") (pin "P$1") (pinfunction "S_P$1") (pintype "bidirectional"))
    )
    (net (code "39") (name "Net-(U$9-D)") (class "Default")
      (node (ref "R18") (pin "1") (pinfunction "1_1") (pintype "passive"))
      (node (ref "U$9") (pin "3") (pinfunction "D_3") (pintype "bidirectional"))
    )
    (net (code "40") (name "Net-(U$9-G)") (class "Default")
      (node (ref "R19") (pin "1") (pinfunction "1_1") (pintype "passive"))
      (node (ref "U$27") (pin "ENOUT") (pinfunction "ENOUT_ENOUT") (pintype "bidirectional"))
      (node (ref "U$9") (pin "1") (pinfunction "G_1") (pintype "passive"))
    )
    (net (code "41") (name "Net-(U$10-D)") (class "Default")
      (node (ref "R29") (pin "1") (pinfunction "1_1") (pintype "passive"))
      (node (ref "U$10") (pin "3") (pinfunction "D_3") (pintype "bidirectional"))
    )
    (net (code "42") (name "Net-(U$10-G)") (class "Default")
      (node (ref "R30") (pin "1") (pinfunction "1_1") (pintype "passive"))
      (node (ref "U$1") (pin "ENOUT") (pinfunction "ENOUT_ENOUT") (pintype "bidirectional"))
      (node (ref "U$10") (pin "1") (pinfunction "G_1") (pintype "passive"))
    )
    (net (code "43") (name "Net-(U$13-C)") (class "Default")
      (node (ref "BATT2_IN") (pin "P$1") (pinfunction "P$1_P$1") (pintype "bidirectional"))
      (node (ref "R36") (pin "1") (pinfunction "1_1") (pintype "passive"))
      (node (ref "U$13") (pin "P$2") (pinfunction "C_P$2") (pintype "passive"))
      (node (ref "U$19") (pin "TAB") (pinfunction "D_TAB") (pintype "passive"))
    )
    (net (code "44") (name "Net-(U$14-D)") (class "Default")
      (node (ref "BATT1_IN") (pin "P$1") (pinfunction "P$1_P$1") (pintype "bidirectional"))
      (node (ref "R38") (pin "1") (pinfunction "1_1") (pintype "passive"))
      (node (ref "U$14") (pin "TAB") (pinfunction "D_TAB") (pintype "passive"))
      (node (ref "U$5") (pin "P$2") (pinfunction "C_P$2") (pintype "passive"))
    )
    (net (code "45") (name "Net-(U$14-G)") (class "Default")
      (node (ref "C3") (pin "1") (pinfunction "1_1") (pintype "passive"))
      (node (ref "R37") (pin "1") (pinfunction "1_1") (pintype "passive"))
      (node (ref "U$14") (pin "1") (pinfunction "G_1") (pintype "passive"))
    )
    (net (code "46") (name "Net-(U$19-G)") (class "Default")
      (node (ref "C20") (pin "1") (pinfunction "1_1") (pintype "passive"))
      (node (ref "R35") (pin "1") (pinfunction "1_1") (pintype "passive"))
      (node (ref "U$19") (pin "1") (pinfunction "G_1") (pintype "passive"))
    )
    (net (code "47") (name "Net-(U$27-PadDGATE)") (class "Default")
      (node (ref "U$27") (pin "DGATE") (pinfunction "DGATE_DGATE") (pintype "bidirectional"))
      (node (ref "U$32") (pin "GATE") (pinfunction "GATE_GATE") (pintype "passive"))
    )
    (net (code "48") (name "Net-(U$27-PadSOURCE)") (class "Default")
      (node (ref "U$27") (pin "SOURCE") (pinfunction "SOURCE_SOURCE") (pintype "bidirectional"))
      (node (ref "U$28") (pin "SOURCE1") (pinfunction "SOURCE_SOURCE1") (pintype "passive"))
      (node (ref "U$28") (pin "SOURCE2") (pinfunction "SOURCE_SOURCE2") (pintype "passive"))
      (node (ref "U$28") (pin "SOURCE3") (pinfunction "SOURCE_SOURCE3") (pintype "passive"))
      (node (ref "U$32") (pin "SOURCE1") (pinfunction "SOURCE_SOURCE1") (pintype "passive"))
      (node (ref "U$32") (pin "SOURCE2") (pinfunction "SOURCE_SOURCE2") (pintype "passive"))
      (node (ref "U$32") (pin "SOURCE3") (pinfunction "SOURCE_SOURCE3") (pintype "passive"))
    )
    (net (code "49") (name "Net-(U$27-~{FAULT})") (class "Default")
      (node (ref "R15") (pin "1") (pinfunction "1_1") (pintype "passive"))
      (node (ref "U$27") (pin "FLT") (pinfunction "~{FAULT}_FLT") (pintype "bidirectional"))
      (node (ref "U$8") (pin "P$2") (pinfunction "G_P$2") (pintype "bidirectional"))
    )
    (net (code "50") (name "Net-(U$56-GND)") (class "Default")
      (node (ref "2PIN_5") (pin "P$2") (pinfunction "P$2_P$2") (pintype "bidirectional"))
      (node (ref "C60") (pin "2") (pinfunction "2_2") (pintype "passive"))
      (node (ref "U$56") (pin "P$3") (pinfunction "GND_P$3") (pintype "bidirectional"))
      (node (ref "U$58") (pin "P$1") (pinfunction "A_P$1") (pintype "passive"))
    )
    (net (code "51") (name "Net-(U$56-IN)") (class "Default")
      (node (ref "C60") (pin "1") (pinfunction "1_1") (pintype "passive"))
      (node (ref "R10") (pin "2") (pinfunction "2_2") (pintype "passive"))
      (node (ref "U$56") (pin "P$2") (pinfunction "IN_P$2") (pintype "bidirectional"))
    )
    (net (code "52") (name "Net-(U$56-VDD)") (class "Default")
      (node (ref "C62") (pin "1") (pinfunction "1_1") (pintype "passive"))
      (node (ref "R11") (pin "2") (pinfunction "2_2") (pintype "passive"))
      (node (ref "U$56") (pin "P$5") (pinfunction "VDD_P$5") (pintype "bidirectional"))
      (node (ref "U$57") (pin "P$2") (pinfunction "VOUT_P$2") (pintype "bidirectional"))
      (node (ref "U$57") (pin "P$4") (pinfunction "VOUT_P$4") (pintype "bidirectional"))
    )
    (net (code "53") (name "Net-(U$58-C)") (class "Default")
      (node (ref "2PIN_5") (pin "P$1") (pinfunction "P$1_P$1") (pintype "bidirectional"))
      (node (ref "R10") (pin "1") (pinfunction "1_1") (pintype "passive"))
      (node (ref "R11") (pin "1") (pinfunction "1_1") (pintype "passive"))
      (node (ref "U$58") (pin "P$2") (pinfunction "C_P$2") (pintype "passive"))
    )
  )
)
